# covox.net
KiCad netlist of a schematic drawn in EAGLE
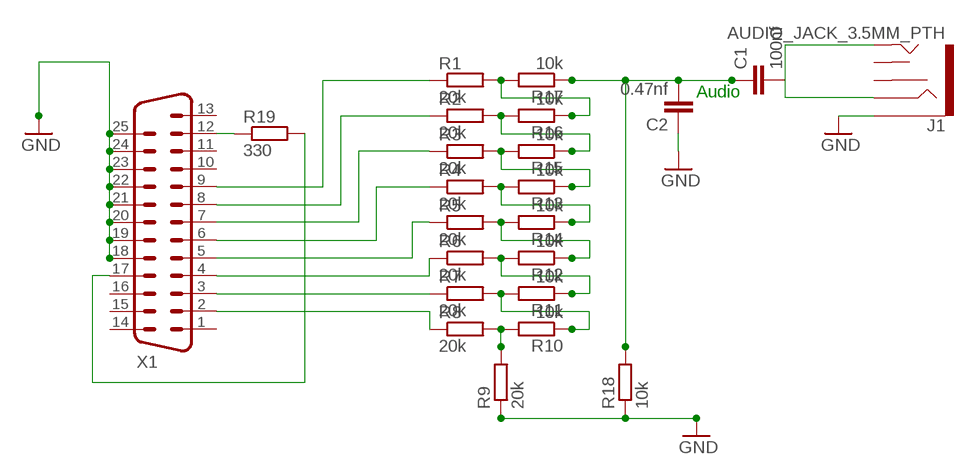
[diagram p0: schematic, sheet 1]

(export (version "E")
  (design (tool "Eeschema 10.0.6"))
  (components
    (comp (ref "C1")
      (value "100nf")
      (footprint "eagle-import:C2.5-2")
      (libsource (lib "eagle-import") (part "C2.5/2"))
    )
    (comp (ref "C2")
      (value "0.47nf")
      (footprint "eagle-import:C2.5-2")
      (libsource (lib "eagle-import") (part "C2.5/2"))
    )
    (comp (ref "J1")
      (value "AUDIO_JACK_3.5MM_PTH")
      (footprint "eagle-import:AUDIO-JACK")
      (libsource (lib "eagle-import") (part "AUDIO_JACK_3.5MM_PTH"))
    )
    (comp (ref "R1")
      (value "20k")
      (footprint "eagle-import:0204_7")
      (libsource (lib "eagle-import") (part "R-EU_0204/7"))
    )
    (comp (ref "R2")
      (value "20k")
      (footprint "eagle-import:0204_7")
      (libsource (lib "eagle-import") (part "R-EU_0204/7"))
    )
    (comp (ref "R3")
      (value "20k")
      (footprint "eagle-import:0204_7")
      (libsource (lib "eagle-import") (part "R-EU_0204/7"))
    )
    (comp (ref "R4")
      (value "20k")
      (footprint "eagle-import:0204_7")
      (libsource (lib "eagle-import") (part "R-EU_0204/7"))
    )
    (comp (ref "R5")
      (value "20k")
      (footprint "eagle-import:0204_7")
      (libsource (lib "eagle-import") (part "R-EU_0204/7"))
    )
    (comp (ref "R6")
      (value "20k")
      (footprint "eagle-import:0204_7")
      (libsource (lib "eagle-import") (part "R-EU_0204/7"))
    )
    (comp (ref "R7")
      (value "20k")
      (footprint "eagle-import:0204_7")
      (libsource (lib "eagle-import") (part "R-EU_0204/7"))
    )
    (comp (ref "R8")
      (value "20k")
      (footprint "eagle-import:0204_7")
      (libsource (lib "eagle-import") (part "R-EU_0204/7"))
    )
    (comp (ref "R9")
      (value "20k")
      (footprint "eagle-import:0204_7")
      (libsource (lib "eagle-import") (part "R-EU_0204/7"))
    )
    (comp (ref "R10")
      (value "10k")
      (footprint "eagle-import:0204_7")
      (libsource (lib "eagle-import") (part "R-EU_0204/7"))
    )
    (comp (ref "R11")
      (value "10k")
      (footprint "eagle-import:0204_7")
      (libsource (lib "eagle-import") (part "R-EU_0204/7"))
    )
    (comp (ref "R12")
      (value "10k")
      (footprint "eagle-import:0204_7")
      (libsource (lib "eagle-import") (part "R-EU_0204/7"))
    )
    (comp (ref "R13")
      (value "10k")
      (footprint "eagle-import:0204_7")
      (libsource (lib "eagle-import") (part "R-EU_0204/7"))
    )
    (comp (ref "R14")
      (value "10k")
      (footprint "eagle-import:0204_7")
      (libsource (lib "eagle-import") (part "R-EU_0204/7"))
    )
    (comp (ref "R15")
      (value "10k")
      (footprint "eagle-import:0204_7")
      (libsource (lib "eagle-import") (part "R-EU_0204/7"))
    )
    (comp (ref "R16")
      (value "10k")
      (footprint "eagle-import:0204_7")
      (libsource (lib "eagle-import") (part "R-EU_0204/7"))
    )
    (comp (ref "R17")
      (value "10k")
      (footprint "eagle-import:0204_7")
      (libsource (lib "eagle-import") (part "R-EU_0204/7"))
    )
    (comp (ref "R18")
      (value "10k")
      (footprint "eagle-import:0204_7")
      (libsource (lib "eagle-import") (part "R-EU_0204/7"))
    )
    (comp (ref "R19")
      (value "330")
      (footprint "eagle-import:0204_7")
      (libsource (lib "eagle-import") (part "R-EU_0204/7"))
    )
    (comp (ref "X1")
      (value "M25HP")
      (footprint "eagle-import:M25HP")
      (libsource (lib "eagle-import") (part "M25HP"))
    )
  )
  (nets
    (net (code "1") (name "GND") (class "Default")
      (node (ref "C2") (pin "1") (pinfunction "1_1") (pintype "passive"))
      (node (ref "J1") (pin "SLEEVE") (pinfunction "SLEEVE_SLEEVE") (pintype "bidirectional"))
      (node (ref "R18") (pin "1") (pinfunction "1_1") (pintype "passive"))
      (node (ref "R9") (pin "1") (pinfunction "1_1") (pintype "passive"))
      (node (ref "X1") (pin "18") (pinfunction "18_18") (pintype "passive"))
      (node (ref "X1") (pin "19") (pinfunction "19_19") (pintype "passive"))
      (node (ref "X1") (pin "20") (pinfunction "20_20") (pintype "passive"))
      (node (ref "X1") (pin "21") (pinfunction "21_21") (pintype "passive"))
      (node (ref "X1") (pin "22") (pinfunction "22_22") (pintype "passive"))
      (node (ref "X1") (pin "23") (pinfunction "23_23") (pintype "passive"))
      (node (ref "X1") (pin "24") (pinfunction "24_24") (pintype "passive"))
      (node (ref "X1") (pin "25") (pinfunction "25_25") (pintype "passive"))
    )
    (net (code "2") (name "Net-(C1-Pad1)") (class "Default")
      (node (ref "C1") (pin "1") (pinfunction "1_1") (pintype "passive"))
      (node (ref "C2") (pin "2") (pinfunction "2_2") (pintype "passive"))
      (node (ref "R17") (pin "1") (pinfunction "1_1") (pintype "passive"))
      (node (ref "R18") (pin "2") (pinfunction "2_2") (pintype "passive"))
    )
    (net (code "3") (name "Net-(C1-Pad2)") (class "Default")
      (node (ref "C1") (pin "2") (pinfunction "2_2") (pintype "passive"))
      (node (ref "J1") (pin "RING") (pinfunction "RING_RING") (pintype "bidirectional"))
      (node (ref "J1") (pin "TIP") (pinfunction "TIP_TIP") (pintype "bidirectional"))
    )
    (net (code "4") (name "Net-(R1-Pad1)") (class "Default")
      (node (ref "R1") (pin "1") (pinfunction "1_1") (pintype "passive"))
      (node (ref "X1") (pin "9") (pinfunction "9_9") (pintype "passive"))
    )
    (net (code "5") (name "Net-(R1-Pad2)") (class "Default")
      (node (ref "R1") (pin "2") (pinfunction "2_2") (pintype "passive"))
      (node (ref "R16") (pin "1") (pinfunction "1_1") (pintype "passive"))
      (node (ref "R17") (pin "2") (pinfunction "2_2") (pintype "passive"))
    )
    (net (code "6") (name "Net-(R2-Pad1)") (class "Default")
      (node (ref "R2") (pin "1") (pinfunction "1_1") (pintype "passive"))
      (node (ref "X1") (pin "8") (pinfunction "8_8") (pintype "passive"))
    )
    (net (code "7") (name "Net-(R3-Pad1)") (class "Default")
      (node (ref "R3") (pin "1") (pinfunction "1_1") (pintype "passive"))
      (node (ref "X1") (pin "7") (pinfunction "7_7") (pintype "passive"))
    )
    (net (code "8") (name "Net-(R4-Pad1)") (class "Default")
      (node (ref "R4") (pin "1") (pinfunction "1_1") (pintype "passive"))
      (node (ref "X1") (pin "6") (pinfunction "6_6") (pintype "passive"))
    )
    (net (code "9") (name "Net-(R5-Pad1)") (class "Default")
      (node (ref "R5") (pin "1") (pinfunction "1_1") (pintype "passive"))
      (node (ref "X1") (pin "5") (pinfunction "5_5") (pintype "passive"))
    )
    (net (code "10") (name "Net-(R6-Pad1)") (class "Default")
      (node (ref "R6") (pin "1") (pinfunction "1_1") (pintype "passive"))
      (node (ref "X1") (pin "4") (pinfunction "4_4") (pintype "passive"))
    )
    (net (code "11") (name "Net-(R7-Pad1)") (class "Default")
      (node (ref "R7") (pin "1") (pinfunction "1_1") (pintype "passive"))
      (node (ref "X1") (pin "3") (pinfunction "3_3") (pintype "passive"))
    )
    (net (code "12") (name "Net-(R8-Pad1)") (class "Default")
      (node (ref "R8") (pin "1") (pinfunction "1_1") (pintype "passive"))
      (node (ref "X1") (pin "2") (pinfunction "2_2") (pintype "passive"))
    )
    (net (code "13") (name "Net-(R10-Pad1)") (class "Default")
      (node (ref "R10") (pin "1") (pinfunction "1_1") (pintype "passive"))
      (node (ref "R11") (pin "2") (pinfunction "2_2") (pintype "passive"))
      (node (ref "R7") (pin "2") (pinfunction "2_2") (pintype "passive"))
    )
    (net (code "14") (name "Net-(R10-Pad2)") (class "Default")
      (node (ref "R10") (pin "2") (pinfunction "2_2") (pintype "passive"))
      (node (ref "R8") (pin "2") (pinfunction "2_2") (pintype "passive"))
      (node (ref "R9") (pin "2") (pinfunction "2_2") (pintype "passive"))
    )
    (net (code "15") (name "Net-(R11-Pad1)") (class "Default")
      (node (ref "R11") (pin "1") (pinfunction "1_1") (pintype "passive"))
      (node (ref "R12") (pin "2") (pinfunction "2_2") (pintype "passive"))
      (node (ref "R6") (pin "2") (pinfunction "2_2") (pintype "passive"))
    )
    (net (code "16") (name "Net-(R12-Pad1)") (class "Default")
      (node (ref "R12") (pin "1") (pinfunction "1_1") (pintype "passive"))
      (node (ref "R14") (pin "2") (pinfunction "2_2") (pintype "passive"))
      (node (ref "R5") (pin "2") (pinfunction "2_2") (pintype "passive"))
    )
    (net (code "17") (name "Net-(R13-Pad1)") (class "Default")
      (node (ref "R13") (pin "1") (pinfunction "1_1") (pintype "passive"))
      (node (ref "R15") (pin "2") (pinfunction "2_2") (pintype "passive"))
      (node (ref "R3") (pin "2") (pinfunction "2_2") (pintype "passive"))
    )
    (net (code "18") (name "Net-(R13-Pad2)") (class "Default")
      (node (ref "R13") (pin "2") (pinfunction "2_2") (pintype "passive"))
      (node (ref "R14") (pin "1") (pinfunction "1_1") (pintype "passive"))
      (node (ref "R4") (pin "2") (pinfunction "2_2") (pintype "passive"))
    )
    (net (code "19") (name "Net-(R15-Pad1)") (class "Default")
      (node (ref "R15") (pin "1") (pinfunction "1_1") (pintype "passive"))
      (node (ref "R16") (pin "2") (pinfunction "2_2") (pintype "passive"))
      (node (ref "R2") (pin "2") (pinfunction "2_2") (pintype "passive"))
    )
    (net (code "20") (name "Net-(R19-Pad1)") (class "Default")
      (node (ref "R19") (pin "1") (pinfunction "1_1") (pintype "passive"))
      (node (ref "X1") (pin "12") (pinfunction "12_12") (pintype "passive"))
    )
    (net (code "21") (name "Net-(R19-Pad2)") (class "Default")
      (node (ref "R19") (pin "2") (pinfunction "2_2") (pintype "passive"))
      (node (ref "X1") (pin "17") (pinfunction "17_17") (pintype "passive"))
    )
    (net (code "22") (name "unconnected-(J1-PadRSH)") (class "Default")
      (node (ref "J1") (pin "RSH") (pinfunction "RSH_RSH") (pintype "bidirectional"))
    )
    (net (code "23") (name "unconnected-(J1-PadTSH)") (class "Default")
      (node (ref "J1") (pin "TSH") (pinfunction "TSH_TSH") (pintype "bidirectional"))
    )
    (net (code "24") (name "unconnected-(X1-Pad1)") (class "Default")
      (node (ref "X1") (pin "1") (pinfunction "1_1") (pintype "passive"))
    )
    (net (code "25") (name "unconnected-(X1-Pad10)") (class "Default")
      (node (ref "X1") (pin "10") (pinfunction "10_10") (pintype "passive"))
    )
    (net (code "26") (name "unconnected-(X1-Pad11)") (class "Default")
      (node (ref "X1") (pin "11") (pinfunction "11_11") (pintype "passive"))
    )
    (net (code "27") (name "unconnected-(X1-Pad13)") (class "Default")
      (node (ref "X1") (pin "13") (pinfunction "13_13") (pintype "passive"))
    )
    (net (code "28") (name "unconnected-(X1-Pad14)") (class "Default")
      (node (ref "X1") (pin "14") (pinfunction "14_14") (pintype "passive"))
    )
    (net (code "29") (name "unconnected-(X1-Pad15)") (class "Default")
      (node (ref "X1") (pin "15") (pinfunction "15_15") (pintype "passive"))
    )
    (net (code "30") (name "unconnected-(X1-Pad16)") (class "Default")
      (node (ref "X1") (pin "16") (pinfunction "16_16") (pintype "passive"))
    )
  )
)
